# ProPrj_12V_5V__2025-09-23.net
KiCad netlist of a schematic drawn in EasyEDA Pro
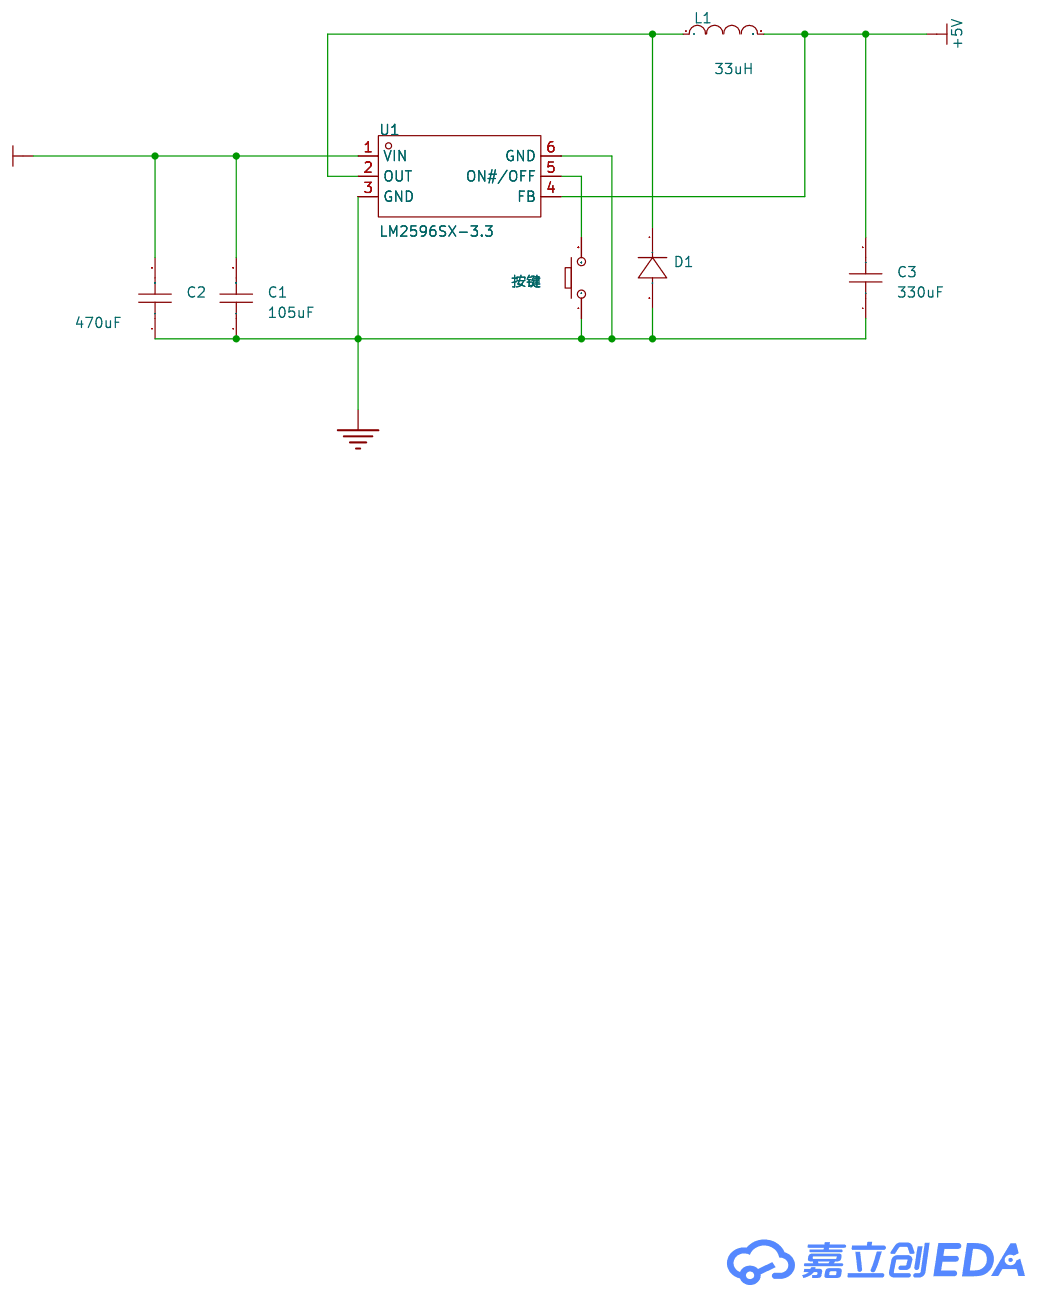
[diagram p0: schematic sheet]

(export (version "E")
  (design (tool "Eeschema 10.0.6"))
  (components
    (comp (ref "C1")
      (value "105uF")
      (footprint "easyedapro:C0603")
      (libsource (lib "easyedapro") (part "CapAcitance"))
    )
    (comp (ref "C2")
      (value "470uF")
      (footprint "easyedapro:C0603")
      (libsource (lib "easyedapro") (part "CapAcitance"))
    )
    (comp (ref "C3")
      (value "330uF")
      (footprint "easyedapro:C0603")
      (libsource (lib "easyedapro") (part "CapAcitance"))
    )
    (comp (ref "D1")
      (value "~")
      (footprint "easyedapro:DO_1N4007")
      (libsource (lib "easyedapro") (part "D_1N4007"))
    )
    (comp (ref "L1")
      (value "33uH")
      (footprint "easyedapro:L0603")
      (libsource (lib "easyedapro") (part "SDFL1608S100KTF"))
    )
    (comp (ref "U1")
      (value "LM2596SX-3.3")
      (footprint "easyedapro:TO-263-5_L10.2-W8.6-P1.70-LS14.4-TL")
      (description "功能类型:降压型;工作电压:4.5V~40V;输出电压:3.168V~3.432V;输出电流:3A;")
      (fields (field (name "Manufacturer") "Slkor(萨科微)"))
      (libsource (lib "easyedapro") (part "LM2596SX-3.3"))
    )
    (comp (ref "按键")
      (value "~")
      (footprint "easyedapro:Key_TH_3.5x6x4.3")
      (libsource (lib "easyedapro") (part "Key_TH_3.5x6x4.3"))
    )
  )
  (nets
    (net (code "1") (name "+5V") (class "Default")
      (node (ref "C3") (pin "2") (pinfunction "2_2") (pintype "input"))
      (node (ref "L1") (pin "2") (pinfunction "2_2") (pintype "unspecified"))
      (node (ref "U1") (pin "4") (pinfunction "FB_4") (pintype "unspecified"))
    )
    (net (code "2") (name "+12V") (class "Default")
      (node (ref "C1") (pin "2") (pinfunction "2_2") (pintype "input"))
      (node (ref "C2") (pin "2") (pinfunction "2_2") (pintype "input"))
      (node (ref "U1") (pin "1") (pinfunction "VIN_1") (pintype "unspecified"))
    )
    (net (code "3") (name "GND") (class "Default")
      (node (ref "C1") (pin "1") (pinfunction "1_1") (pintype "input"))
      (node (ref "C2") (pin "1") (pinfunction "1_1") (pintype "input"))
      (node (ref "C3") (pin "1") (pinfunction "1_1") (pintype "input"))
      (node (ref "D1") (pin "2") (pinfunction "A_2") (pintype "input"))
      (node (ref "U1") (pin "3") (pinfunction "GND_3") (pintype "unspecified"))
      (node (ref "U1") (pin "6") (pinfunction "GND_6") (pintype "unspecified"))
      (node (ref "按键") (pin "A") (pinfunction "A_A") (pintype "input"))
    )
    (net (code "4") (name "Net-(D1-K)") (class "Default")
      (node (ref "D1") (pin "1") (pinfunction "K_1") (pintype "input"))
      (node (ref "L1") (pin "1") (pinfunction "1_1") (pintype "unspecified"))
      (node (ref "U1") (pin "2") (pinfunction "OUT_2") (pintype "unspecified"))
    )
    (net (code "5") (name "Net-(U1-ON#{slash}OFF)") (class "Default")
      (node (ref "U1") (pin "5") (pinfunction "ON#/OFF_5") (pintype "unspecified"))
      (node (ref "按键") (pin "B") (pinfunction "B_B") (pintype "input"))
    )
  )
)
